# Schematic.net
KiCad netlist of a schematic drawn in EasyEDA
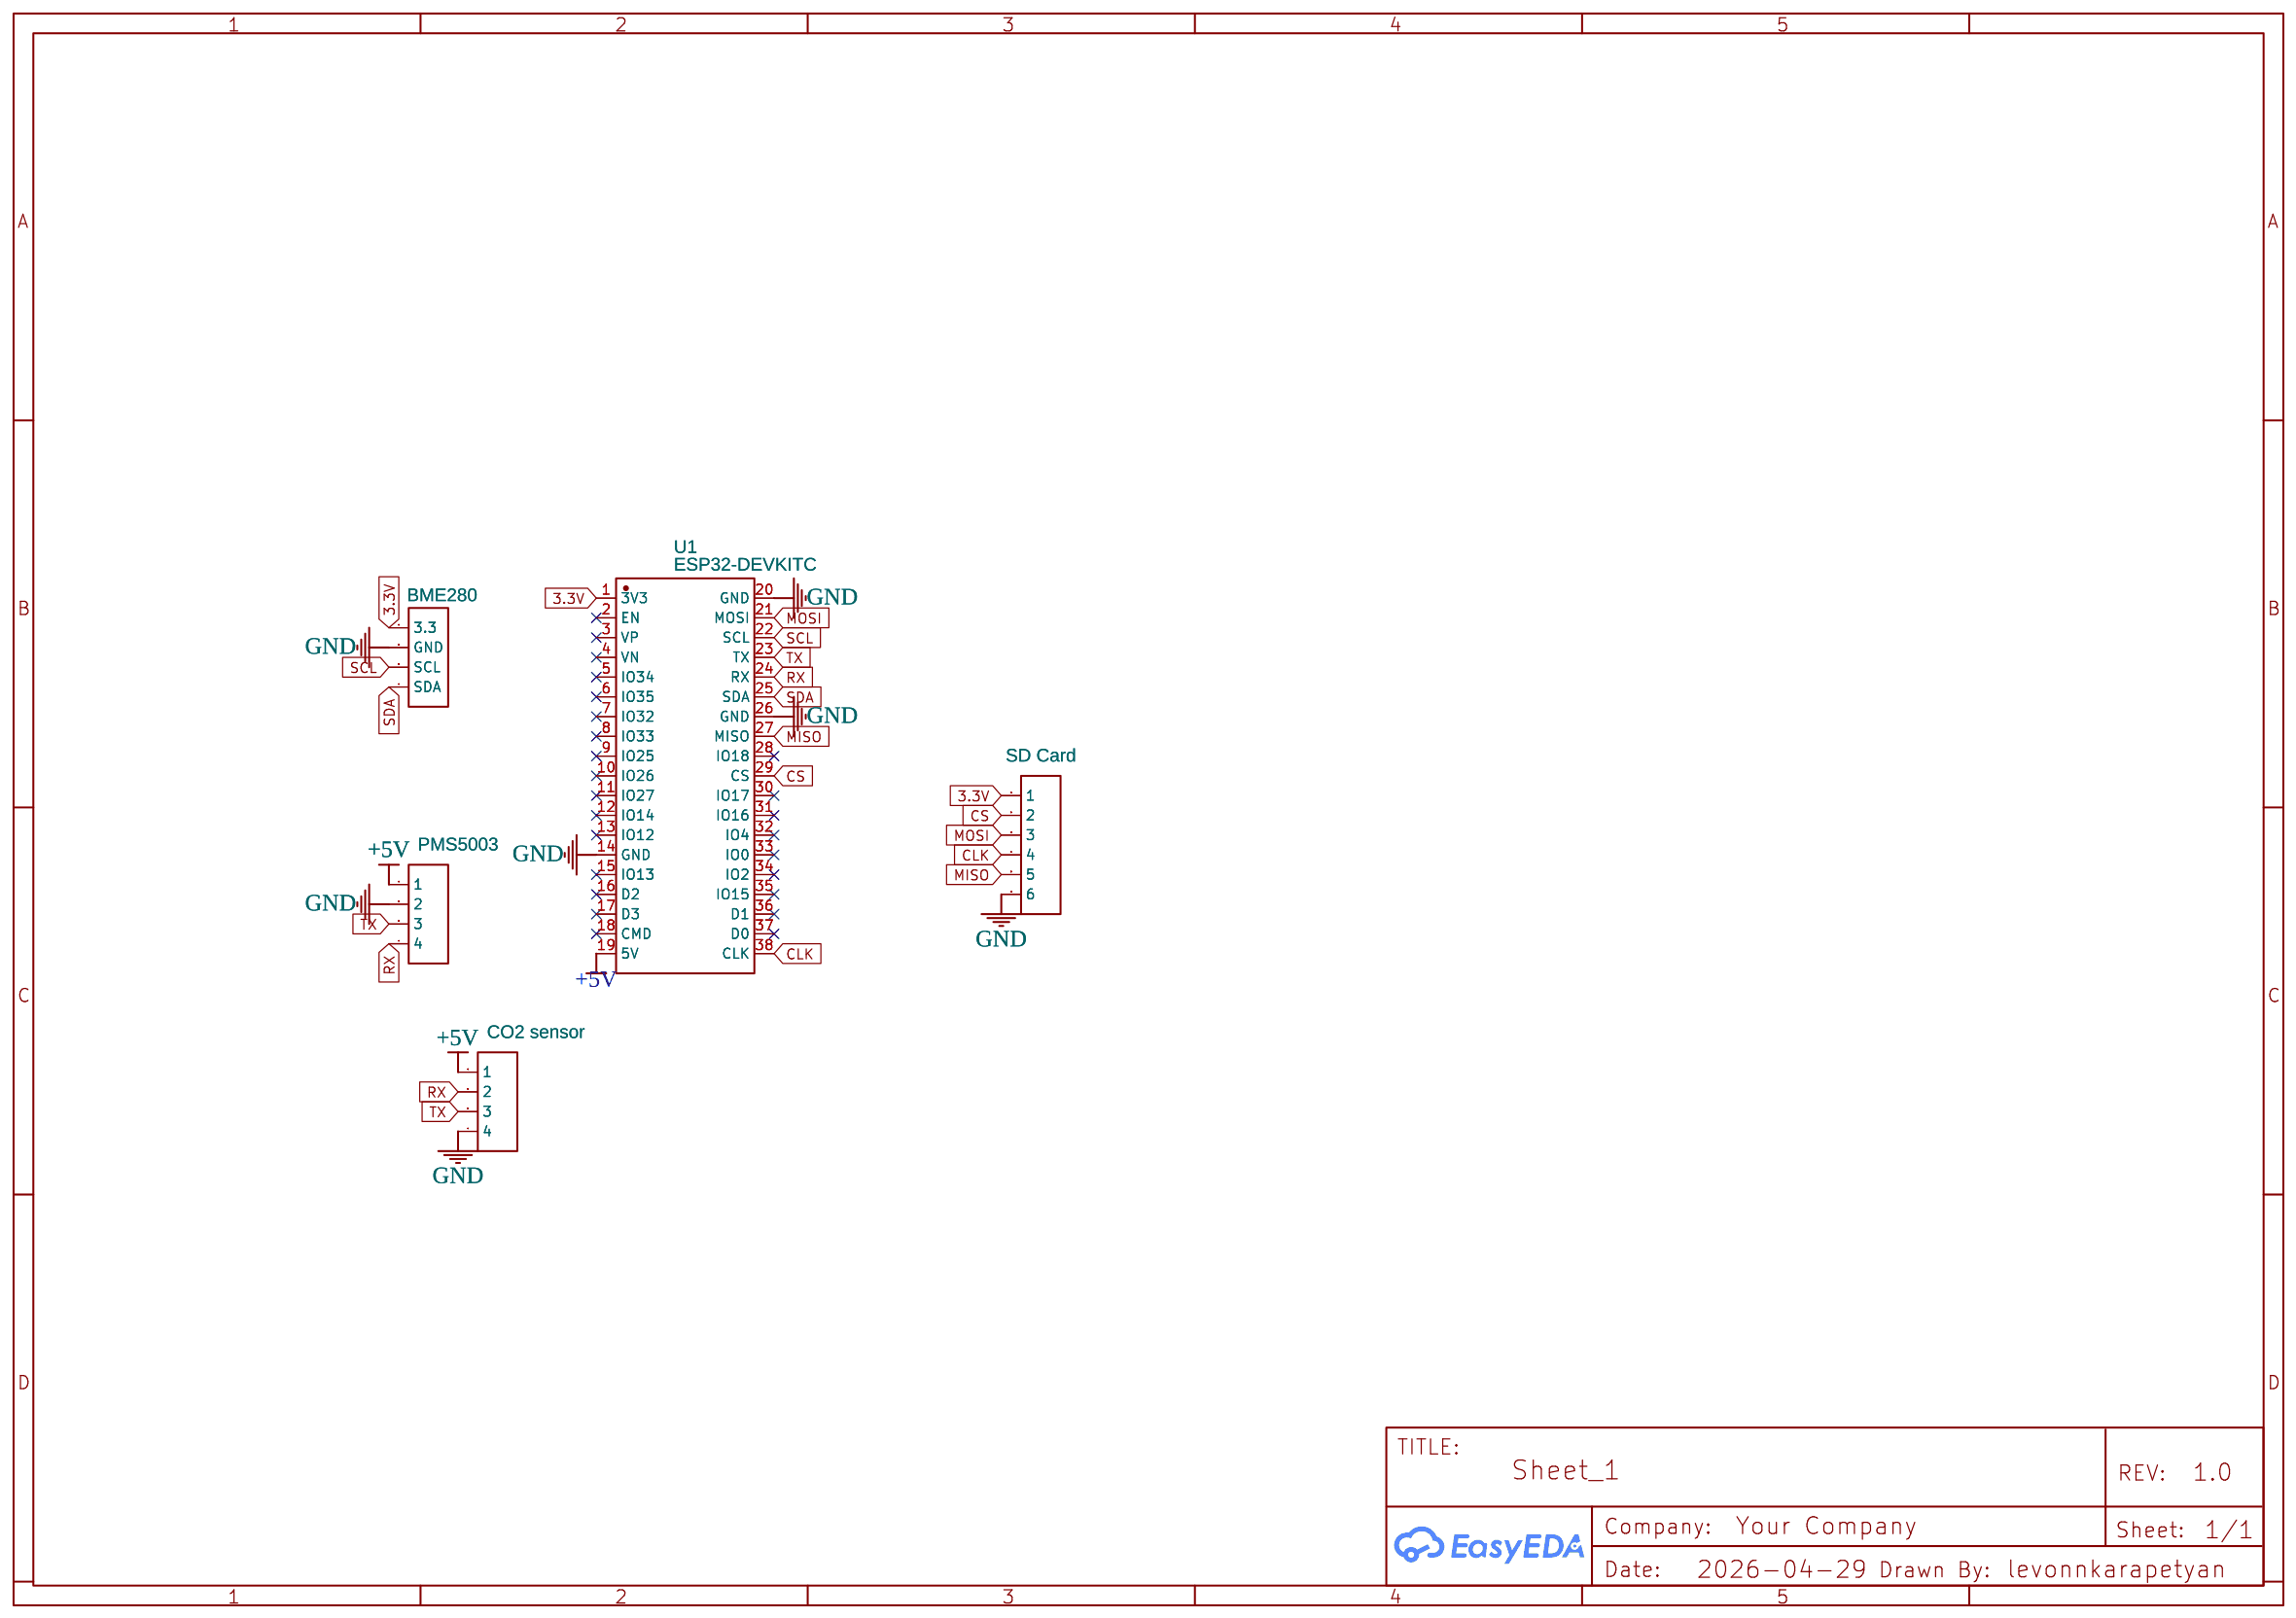
[diagram p0: schematic sheet]

(export (version "E")
  (design (tool "Eeschema 10.0.6"))
  (components
    (comp (ref "J1") (value "PMS5003") (libsource (lib "") (part "HDR-M-2.54_1x4_1")))
    (comp (ref "J2") (value "BME280") (libsource (lib "") (part "HDR-M-2.54_1x4")))
    (comp (ref "J3") (value "CO2 sensor") (libsource (lib "") (part "HDR-M-2.54_1x4_1")))
    (comp (ref "J4") (value "SD Card") (libsource (lib "") (part "HDR-M-2.54_1x6")))
    (comp (ref "U1")
      (value "ESP32-DEVKITC")
      (fields
        (field (name "Manufacturer Part") "ESP32-DevKitC")
        (field (name "Manufacturer") "ESPRESSIF(乐鑫)")
      )
      (libsource (lib "") (part "ESP32-DEVKITC"))
    )
  )
  (nets
    (net (code "1") (name "+5V") (class "Default")
      (node (ref "J1") (pin "1") (pinfunction "1_1") (pintype "unspecified"))
      (node (ref "J3") (pin "1") (pinfunction "1_1") (pintype "unspecified"))
      (node (ref "U1") (pin "19") (pinfunction "5V_19") (pintype "unspecified"))
    )
    (net (code "2") (name "3.3V") (class "Default")
      (node (ref "J2") (pin "1") (pinfunction "3.3_1") (pintype "unspecified"))
      (node (ref "J4") (pin "1") (pinfunction "1_1") (pintype "input"))
      (node (ref "U1") (pin "1") (pinfunction "3V3_1") (pintype "unspecified"))
    )
    (net (code "3") (name "CLK") (class "Default")
      (node (ref "J4") (pin "4") (pinfunction "4_4") (pintype "input"))
      (node (ref "U1") (pin "38") (pinfunction "CLK_38") (pintype "unspecified"))
    )
    (net (code "4") (name "CS") (class "Default")
      (node (ref "J4") (pin "2") (pinfunction "2_2") (pintype "input"))
      (node (ref "U1") (pin "29") (pinfunction "CS_29") (pintype "unspecified"))
    )
    (net (code "5") (name "GND") (class "Default")
      (node (ref "J1") (pin "2") (pinfunction "2_2") (pintype "unspecified"))
      (node (ref "J2") (pin "2") (pinfunction "GND_2") (pintype "unspecified"))
      (node (ref "J3") (pin "4") (pinfunction "4_4") (pintype "unspecified"))
      (node (ref "J4") (pin "6") (pinfunction "6_6") (pintype "input"))
      (node (ref "U1") (pin "14") (pinfunction "GND_14") (pintype "unspecified"))
      (node (ref "U1") (pin "20") (pinfunction "GND_20") (pintype "unspecified"))
      (node (ref "U1") (pin "26") (pinfunction "GND_26") (pintype "unspecified"))
    )
    (net (code "6") (name "MISO") (class "Default")
      (node (ref "J4") (pin "5") (pinfunction "5_5") (pintype "input"))
      (node (ref "U1") (pin "27") (pinfunction "MISO_27") (pintype "unspecified"))
    )
    (net (code "7") (name "MOSI") (class "Default")
      (node (ref "J4") (pin "3") (pinfunction "3_3") (pintype "input"))
      (node (ref "U1") (pin "21") (pinfunction "MOSI_21") (pintype "unspecified"))
    )
    (net (code "8") (name "RX") (class "Default")
      (node (ref "J1") (pin "4") (pinfunction "4_4") (pintype "unspecified"))
      (node (ref "J3") (pin "2") (pinfunction "2_2") (pintype "unspecified"))
      (node (ref "U1") (pin "24") (pinfunction "RX_24") (pintype "unspecified"))
    )
    (net (code "9") (name "SCL") (class "Default")
      (node (ref "J2") (pin "3") (pinfunction "SCL_3") (pintype "unspecified"))
      (node (ref "U1") (pin "22") (pinfunction "SCL_22") (pintype "unspecified"))
    )
    (net (code "10") (name "SDA") (class "Default")
      (node (ref "J2") (pin "4") (pinfunction "SDA_4") (pintype "unspecified"))
      (node (ref "U1") (pin "25") (pinfunction "SDA_25") (pintype "unspecified"))
    )
    (net (code "11") (name "TX") (class "Default")
      (node (ref "J1") (pin "3") (pinfunction "3_3") (pintype "unspecified"))
      (node (ref "J3") (pin "3") (pinfunction "3_3") (pintype "unspecified"))
      (node (ref "U1") (pin "23") (pinfunction "TX_23") (pintype "unspecified"))
    )
    (net (code "12") (name "unconnected-(U1-CMD-Pad18)") (class "Default")
      (node (ref "U1") (pin "18") (pinfunction "CMD_18") (pintype "unspecified+no_connect"))
    )
    (net (code "13") (name "unconnected-(U1-D0-Pad37)") (class "Default")
      (node (ref "U1") (pin "37") (pinfunction "D0_37") (pintype "unspecified+no_connect"))
    )
    (net (code "14") (name "unconnected-(U1-D1-Pad36)") (class "Default")
      (node (ref "U1") (pin "36") (pinfunction "D1_36") (pintype "unspecified+no_connect"))
    )
    (net (code "15") (name "unconnected-(U1-D2-Pad16)") (class "Default")
      (node (ref "U1") (pin "16") (pinfunction "D2_16") (pintype "unspecified+no_connect"))
    )
    (net (code "16") (name "unconnected-(U1-D3-Pad17)") (class "Default")
      (node (ref "U1") (pin "17") (pinfunction "D3_17") (pintype "unspecified+no_connect"))
    )
    (net (code "17") (name "unconnected-(U1-EN-Pad2)") (class "Default")
      (node (ref "U1") (pin "2") (pinfunction "EN_2") (pintype "unspecified+no_connect"))
    )
    (net (code "18") (name "unconnected-(U1-IO0-Pad33)") (class "Default")
      (node (ref "U1") (pin "33") (pinfunction "IO0_33") (pintype "unspecified+no_connect"))
    )
    (net (code "19") (name "unconnected-(U1-IO2-Pad34)") (class "Default")
      (node (ref "U1") (pin "34") (pinfunction "IO2_34") (pintype "unspecified+no_connect"))
    )
    (net (code "20") (name "unconnected-(U1-IO4-Pad32)") (class "Default")
      (node (ref "U1") (pin "32") (pinfunction "IO4_32") (pintype "unspecified+no_connect"))
    )
    (net (code "21") (name "unconnected-(U1-IO12-Pad13)") (class "Default")
      (node (ref "U1") (pin "13") (pinfunction "IO12_13") (pintype "unspecified+no_connect"))
    )
    (net (code "22") (name "unconnected-(U1-IO13-Pad15)") (class "Default")
      (node (ref "U1") (pin "15") (pinfunction "IO13_15") (pintype "unspecified+no_connect"))
    )
    (net (code "23") (name "unconnected-(U1-IO14-Pad12)") (class "Default")
      (node (ref "U1") (pin "12") (pinfunction "IO14_12") (pintype "unspecified+no_connect"))
    )
    (net (code "24") (name "unconnected-(U1-IO15-Pad35)") (class "Default")
      (node (ref "U1") (pin "35") (pinfunction "IO15_35") (pintype "unspecified+no_connect"))
    )
    (net (code "25") (name "unconnected-(U1-IO16-Pad31)") (class "Default")
      (node (ref "U1") (pin "31") (pinfunction "IO16_31") (pintype "unspecified+no_connect"))
    )
    (net (code "26") (name "unconnected-(U1-IO17-Pad30)") (class "Default")
      (node (ref "U1") (pin "30") (pinfunction "IO17_30") (pintype "unspecified+no_connect"))
    )
    (net (code "27") (name "unconnected-(U1-IO18-Pad28)") (class "Default")
      (node (ref "U1") (pin "28") (pinfunction "IO18_28") (pintype "unspecified+no_connect"))
    )
    (net (code "28") (name "unconnected-(U1-IO25-Pad9)") (class "Default")
      (node (ref "U1") (pin "9") (pinfunction "IO25_9") (pintype "unspecified+no_connect"))
    )
    (net (code "29") (name "unconnected-(U1-IO26-Pad10)") (class "Default")
      (node (ref "U1") (pin "10") (pinfunction "IO26_10") (pintype "unspecified+no_connect"))
    )
    (net (code "30") (name "unconnected-(U1-IO27-Pad11)") (class "Default")
      (node (ref "U1") (pin "11") (pinfunction "IO27_11") (pintype "unspecified+no_connect"))
    )
    (net (code "31") (name "unconnected-(U1-IO32-Pad7)") (class "Default")
      (node (ref "U1") (pin "7") (pinfunction "IO32_7") (pintype "unspecified+no_connect"))
    )
    (net (code "32") (name "unconnected-(U1-IO33-Pad8)") (class "Default")
      (node (ref "U1") (pin "8") (pinfunction "IO33_8") (pintype "unspecified+no_connect"))
    )
    (net (code "33") (name "unconnected-(U1-IO34-Pad5)") (class "Default")
      (node (ref "U1") (pin "5") (pinfunction "IO34_5") (pintype "unspecified+no_connect"))
    )
    (net (code "34") (name "unconnected-(U1-IO35-Pad6)") (class "Default")
      (node (ref "U1") (pin "6") (pinfunction "IO35_6") (pintype "unspecified+no_connect"))
    )
    (net (code "35") (name "unconnected-(U1-VN-Pad4)") (class "Default")
      (node (ref "U1") (pin "4") (pinfunction "VN_4") (pintype "unspecified+no_connect"))
    )
    (net (code "36") (name "unconnected-(U1-VP-Pad3)") (class "Default")
      (node (ref "U1") (pin "3") (pinfunction "VP_3") (pintype "unspecified+no_connect"))
    )
  )
)
